# CH376T.net
KiCad netlist of a schematic drawn in EAGLE
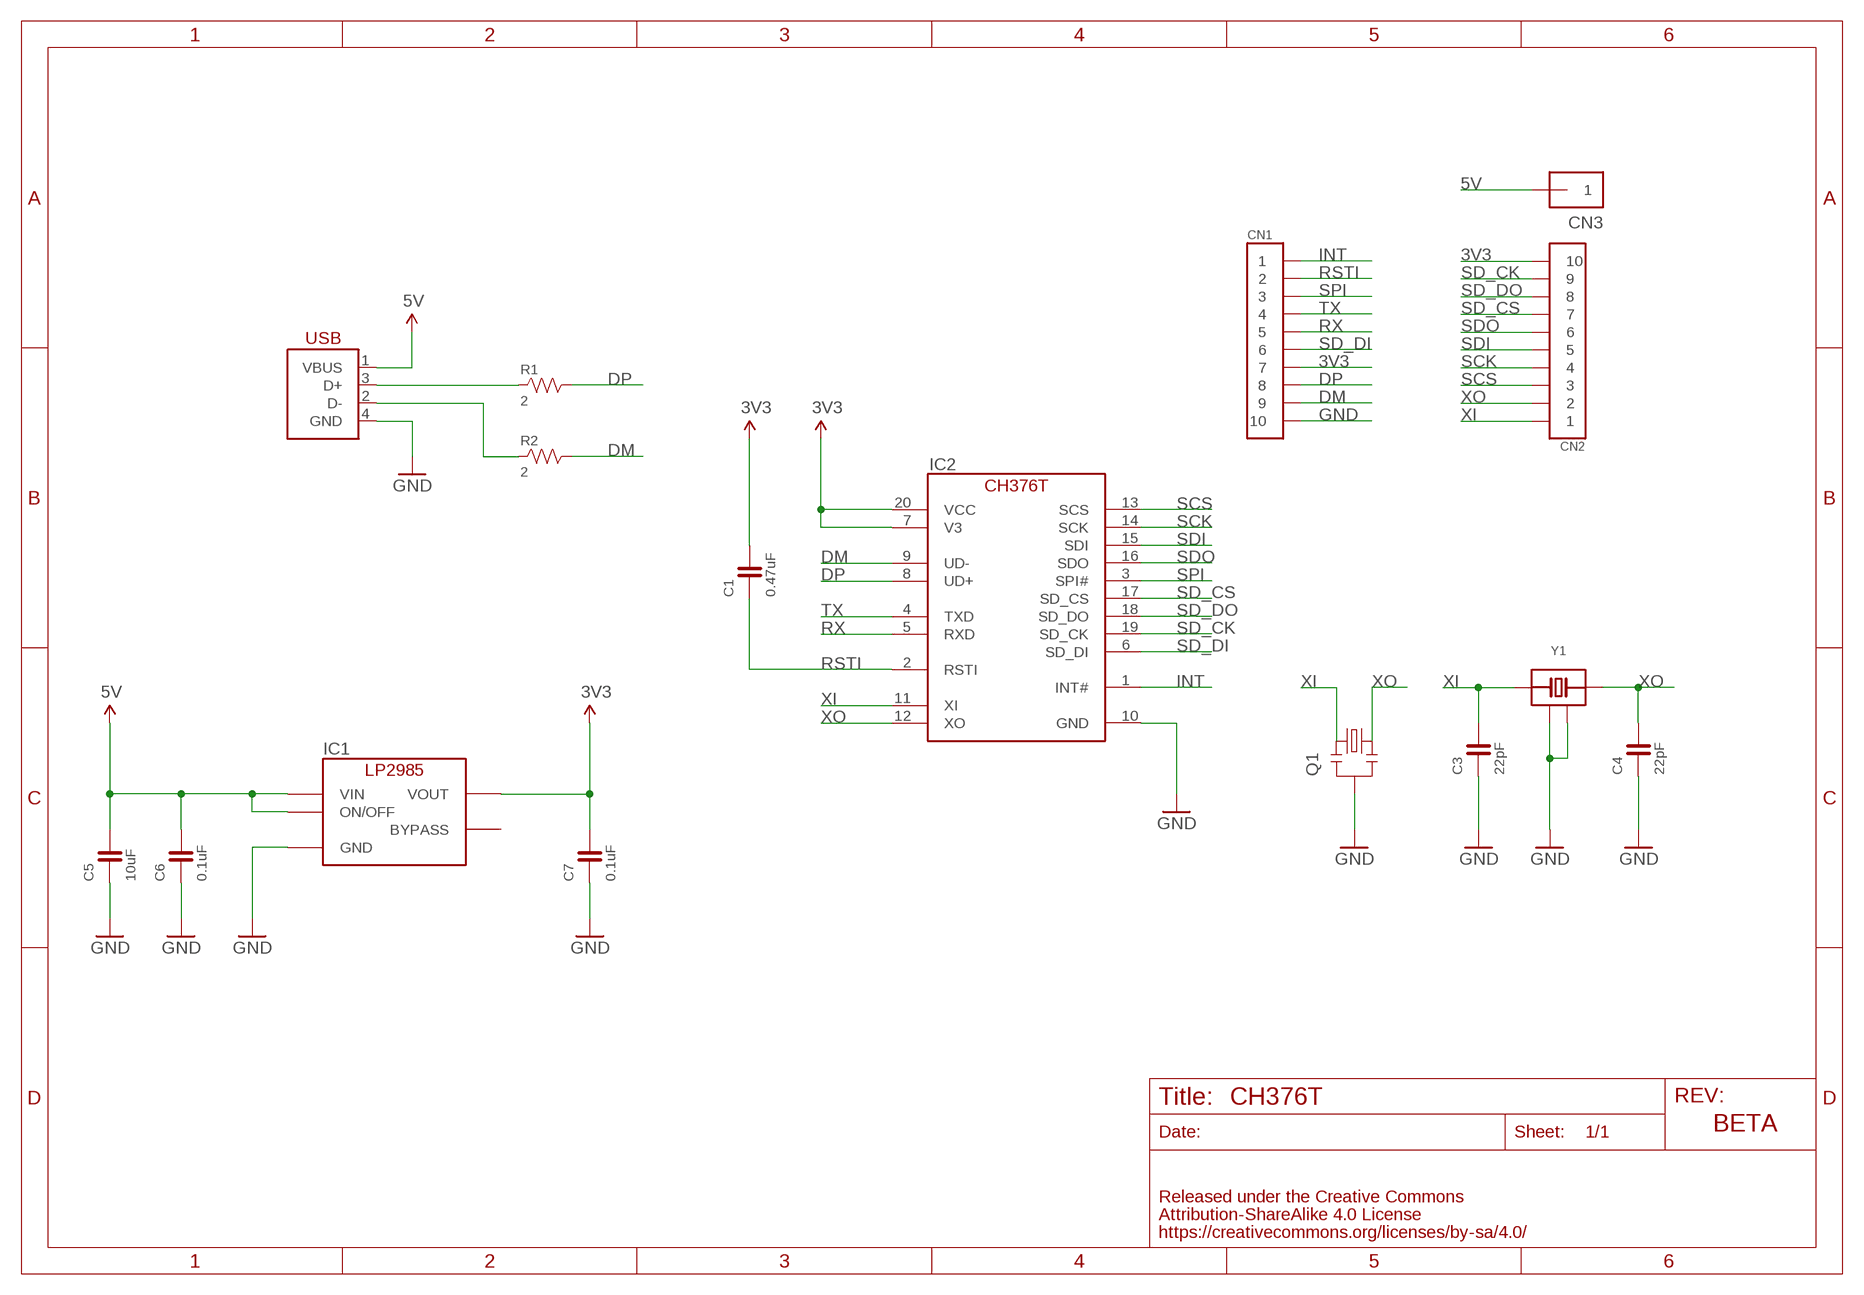
[diagram p0: schematic, sheet 1]

(export (version "E")
  (design (tool "Eeschema 10.0.6"))
  (components
    (comp (ref "C1")
      (value "0.47uF")
      (footprint "eagle-import:0603-NARROW")
      (libsource (lib "eagle-import") (part "CAPACITOR-0603_NARROW"))
    )
    (comp (ref "C3")
      (value "22pF")
      (footprint "eagle-import:0603-NARROW")
      (libsource (lib "eagle-import") (part "CAPACITOR-0603_NARROW"))
    )
    (comp (ref "C4")
      (value "22pF")
      (footprint "eagle-import:0603-NARROW")
      (libsource (lib "eagle-import") (part "CAPACITOR-0603_NARROW"))
    )
    (comp (ref "C5")
      (value "10uF")
      (footprint "eagle-import:0603-NARROW")
      (libsource (lib "eagle-import") (part "CAPACITOR-0603_NARROW"))
    )
    (comp (ref "C6")
      (value "0.1uF")
      (footprint "eagle-import:0603-NARROW")
      (libsource (lib "eagle-import") (part "CAPACITOR-0603_NARROW"))
    )
    (comp (ref "C7")
      (value "0.1uF")
      (footprint "eagle-import:0603-NARROW")
      (libsource (lib "eagle-import") (part "CAPACITOR-0603_NARROW"))
    )
    (comp (ref "CN1")
      (value "PIN_HEADER_1X10")
      (footprint "eagle-import:PIN_1X10")
      (libsource (lib "eagle-import") (part "PIN_HEADER_1X10"))
    )
    (comp (ref "CN2")
      (value "PIN_HEADER_1X10")
      (footprint "eagle-import:PIN_1X10")
      (libsource (lib "eagle-import") (part "PIN_HEADER_1X10"))
    )
    (comp (ref "CN3")
      (value "PIN_HEADER_1X1")
      (footprint "eagle-import:PIN_1X1")
      (libsource (lib "eagle-import") (part "PIN_HEADER_1X1"))
    )
    (comp (ref "IC1")
      (value "LP2985-33DBV")
      (footprint "eagle-import:SOT-23-5")
      (libsource (lib "eagle-import") (part "LP2985-33DBV"))
    )
    (comp (ref "IC2")
      (value "CH376T")
      (footprint "eagle-import:SSOP-20")
      (libsource (lib "eagle-import") (part "CH376T"))
    )
    (comp (ref "Q1")
      (value "RESONATOR-CSTCE_G")
      (footprint "eagle-import:CSTCE_G")
      (libsource (lib "eagle-import") (part "RESONATOR-CSTCE_G"))
    )
    (comp (ref "R1")
      (value "2")
      (footprint "eagle-import:0603-NARROW")
      (libsource (lib "eagle-import") (part "RESISTOR-0603-NARROW"))
    )
    (comp (ref "R2")
      (value "2")
      (footprint "eagle-import:0603-NARROW")
      (libsource (lib "eagle-import") (part "RESISTOR-0603-NARROW"))
    )
    (comp (ref "USB1")
      (value "USB-B_PTH")
      (footprint "eagle-import:USB-4AF103BS")
      (libsource (lib "eagle-import") (part "USB-B_PTH"))
    )
    (comp (ref "Y1")
      (value "CRYSTAL-ECS-120-12-33Q")
      (footprint "eagle-import:ECS-12MHZ")
      (libsource (lib "eagle-import") (part "CRYSTAL-ECS-120-12-33Q"))
    )
  )
  (nets
    (net (code "1") (name "/DM") (class "Default")
      (node (ref "CN1") (pin "9") (pinfunction "9_9") (pintype "bidirectional"))
      (node (ref "IC2") (pin "9") (pinfunction "UD-_9") (pintype "bidirectional"))
      (node (ref "R2") (pin "2") (pinfunction "2_2") (pintype "bidirectional"))
    )
    (net (code "2") (name "/DP") (class "Default")
      (node (ref "CN1") (pin "8") (pinfunction "8_8") (pintype "bidirectional"))
      (node (ref "IC2") (pin "8") (pinfunction "UD+_8") (pintype "bidirectional"))
      (node (ref "R1") (pin "2") (pinfunction "2_2") (pintype "bidirectional"))
    )
    (net (code "3") (name "/INT") (class "Default")
      (node (ref "CN1") (pin "1") (pinfunction "1_1") (pintype "bidirectional"))
      (node (ref "IC2") (pin "1") (pinfunction "INT#_1") (pintype "bidirectional"))
    )
    (net (code "4") (name "/RSTI") (class "Default")
      (node (ref "C1") (pin "1") (pinfunction "1_1") (pintype "passive"))
      (node (ref "CN1") (pin "2") (pinfunction "2_2") (pintype "bidirectional"))
      (node (ref "IC2") (pin "2") (pinfunction "RSTI_2") (pintype "bidirectional"))
    )
    (net (code "5") (name "/RX") (class "Default")
      (node (ref "CN1") (pin "5") (pinfunction "5_5") (pintype "bidirectional"))
      (node (ref "IC2") (pin "5") (pinfunction "RXD_5") (pintype "bidirectional"))
    )
    (net (code "6") (name "/SCK") (class "Default")
      (node (ref "CN2") (pin "4") (pinfunction "4_4") (pintype "bidirectional"))
      (node (ref "IC2") (pin "14") (pinfunction "SCK_14") (pintype "bidirectional"))
    )
    (net (code "7") (name "/SCS") (class "Default")
      (node (ref "CN2") (pin "3") (pinfunction "3_3") (pintype "bidirectional"))
      (node (ref "IC2") (pin "13") (pinfunction "SCS_13") (pintype "bidirectional"))
    )
    (net (code "8") (name "/SDI") (class "Default")
      (node (ref "CN2") (pin "5") (pinfunction "5_5") (pintype "bidirectional"))
      (node (ref "IC2") (pin "15") (pinfunction "SDI_15") (pintype "bidirectional"))
    )
    (net (code "9") (name "/SDO") (class "Default")
      (node (ref "CN2") (pin "6") (pinfunction "6_6") (pintype "bidirectional"))
      (node (ref "IC2") (pin "16") (pinfunction "SDO_16") (pintype "bidirectional"))
    )
    (net (code "10") (name "/SD_CK") (class "Default")
      (node (ref "CN2") (pin "9") (pinfunction "9_9") (pintype "bidirectional"))
      (node (ref "IC2") (pin "19") (pinfunction "SD_CK_19") (pintype "bidirectional"))
    )
    (net (code "11") (name "/SD_CS") (class "Default")
      (node (ref "CN2") (pin "7") (pinfunction "7_7") (pintype "bidirectional"))
      (node (ref "IC2") (pin "17") (pinfunction "SD_CS_17") (pintype "bidirectional"))
    )
    (net (code "12") (name "/SD_DI") (class "Default")
      (node (ref "CN1") (pin "6") (pinfunction "6_6") (pintype "bidirectional"))
      (node (ref "IC2") (pin "6") (pinfunction "SD_DI_6") (pintype "bidirectional"))
    )
    (net (code "13") (name "/SD_DO") (class "Default")
      (node (ref "CN2") (pin "8") (pinfunction "8_8") (pintype "bidirectional"))
      (node (ref "IC2") (pin "18") (pinfunction "SD_DO_18") (pintype "bidirectional"))
    )
    (net (code "14") (name "/SPI") (class "Default")
      (node (ref "CN1") (pin "3") (pinfunction "3_3") (pintype "bidirectional"))
      (node (ref "IC2") (pin "3") (pinfunction "SPI#_3") (pintype "bidirectional"))
    )
    (net (code "15") (name "/TX") (class "Default")
      (node (ref "CN1") (pin "4") (pinfunction "4_4") (pintype "bidirectional"))
      (node (ref "IC2") (pin "4") (pinfunction "TXD_4") (pintype "bidirectional"))
    )
    (net (code "16") (name "/XI") (class "Default")
      (node (ref "C3") (pin "2") (pinfunction "2_2") (pintype "passive"))
      (node (ref "CN2") (pin "1") (pinfunction "1_1") (pintype "bidirectional"))
      (node (ref "IC2") (pin "11") (pinfunction "XI_11") (pintype "bidirectional"))
      (node (ref "Q1") (pin "1") (pinfunction "1_1") (pintype "passive"))
      (node (ref "Y1") (pin "1") (pinfunction "IO_1") (pintype "bidirectional"))
    )
    (net (code "17") (name "/XO") (class "Default")
      (node (ref "C4") (pin "2") (pinfunction "2_2") (pintype "passive"))
      (node (ref "CN2") (pin "2") (pinfunction "2_2") (pintype "bidirectional"))
      (node (ref "IC2") (pin "12") (pinfunction "XO_12") (pintype "bidirectional"))
      (node (ref "Q1") (pin "3") (pinfunction "3_3") (pintype "passive"))
      (node (ref "Y1") (pin "3") (pinfunction "IO_3") (pintype "bidirectional"))
    )
    (net (code "18") (name "3V3") (class "Default")
      (node (ref "C1") (pin "2") (pinfunction "2_2") (pintype "passive"))
      (node (ref "C7") (pin "2") (pinfunction "2_2") (pintype "passive"))
      (node (ref "CN1") (pin "7") (pinfunction "7_7") (pintype "bidirectional"))
      (node (ref "CN2") (pin "10") (pinfunction "10_10") (pintype "bidirectional"))
      (node (ref "IC1") (pin "5") (pinfunction "VOUT_5") (pintype "output"))
      (node (ref "IC2") (pin "20") (pinfunction "VCC_20") (pintype "bidirectional"))
      (node (ref "IC2") (pin "7") (pinfunction "V3_7") (pintype "bidirectional"))
    )
    (net (code "19") (name "5V") (class "Default")
      (node (ref "C5") (pin "2") (pinfunction "2_2") (pintype "passive"))
      (node (ref "C6") (pin "2") (pinfunction "2_2") (pintype "passive"))
      (node (ref "CN3") (pin "1") (pinfunction "1_1") (pintype "bidirectional"))
      (node (ref "IC1") (pin "1") (pinfunction "VIN_1") (pintype "input"))
      (node (ref "IC1") (pin "3") (pinfunction "ON/OFF_3") (pintype "input"))
      (node (ref "USB1") (pin "1") (pinfunction "VBUS_1") (pintype "bidirectional"))
    )
    (net (code "20") (name "GND") (class "Default")
      (node (ref "C3") (pin "1") (pinfunction "1_1") (pintype "passive"))
      (node (ref "C4") (pin "1") (pinfunction "1_1") (pintype "passive"))
      (node (ref "C5") (pin "1") (pinfunction "1_1") (pintype "passive"))
      (node (ref "C6") (pin "1") (pinfunction "1_1") (pintype "passive"))
      (node (ref "C7") (pin "1") (pinfunction "1_1") (pintype "passive"))
      (node (ref "CN1") (pin "10") (pinfunction "10_10") (pintype "bidirectional"))
      (node (ref "IC1") (pin "2") (pinfunction "GND_2") (pintype "power_in"))
      (node (ref "IC2") (pin "10") (pinfunction "GND_10") (pintype "bidirectional"))
      (node (ref "Q1") (pin "2") (pinfunction "2_2") (pintype "passive"))
      (node (ref "USB1") (pin "4") (pinfunction "GND_4") (pintype "bidirectional"))
      (node (ref "Y1") (pin "2") (pinfunction "GND_2") (pintype "bidirectional"))
      (node (ref "Y1") (pin "4") (pinfunction "GND_4") (pintype "bidirectional"))
    )
    (net (code "21") (name "Net-(USB1-D+)") (class "Default")
      (node (ref "R1") (pin "1") (pinfunction "1_1") (pintype "bidirectional"))
      (node (ref "USB1") (pin "3") (pinfunction "D+_3") (pintype "bidirectional"))
    )
    (net (code "22") (name "Net-(USB1-D-)") (class "Default")
      (node (ref "R2") (pin "1") (pinfunction "1_1") (pintype "bidirectional"))
      (node (ref "USB1") (pin "2") (pinfunction "D-_2") (pintype "bidirectional"))
    )
    (net (code "23") (name "unconnected-(IC1-BYPASS-Pad4)") (class "Default")
      (node (ref "IC1") (pin "4") (pinfunction "BYPASS_4") (pintype "bidirectional"))
    )
  )
)
